# FE_Channel.net
KiCad netlist of a schematic drawn in Altium Designer
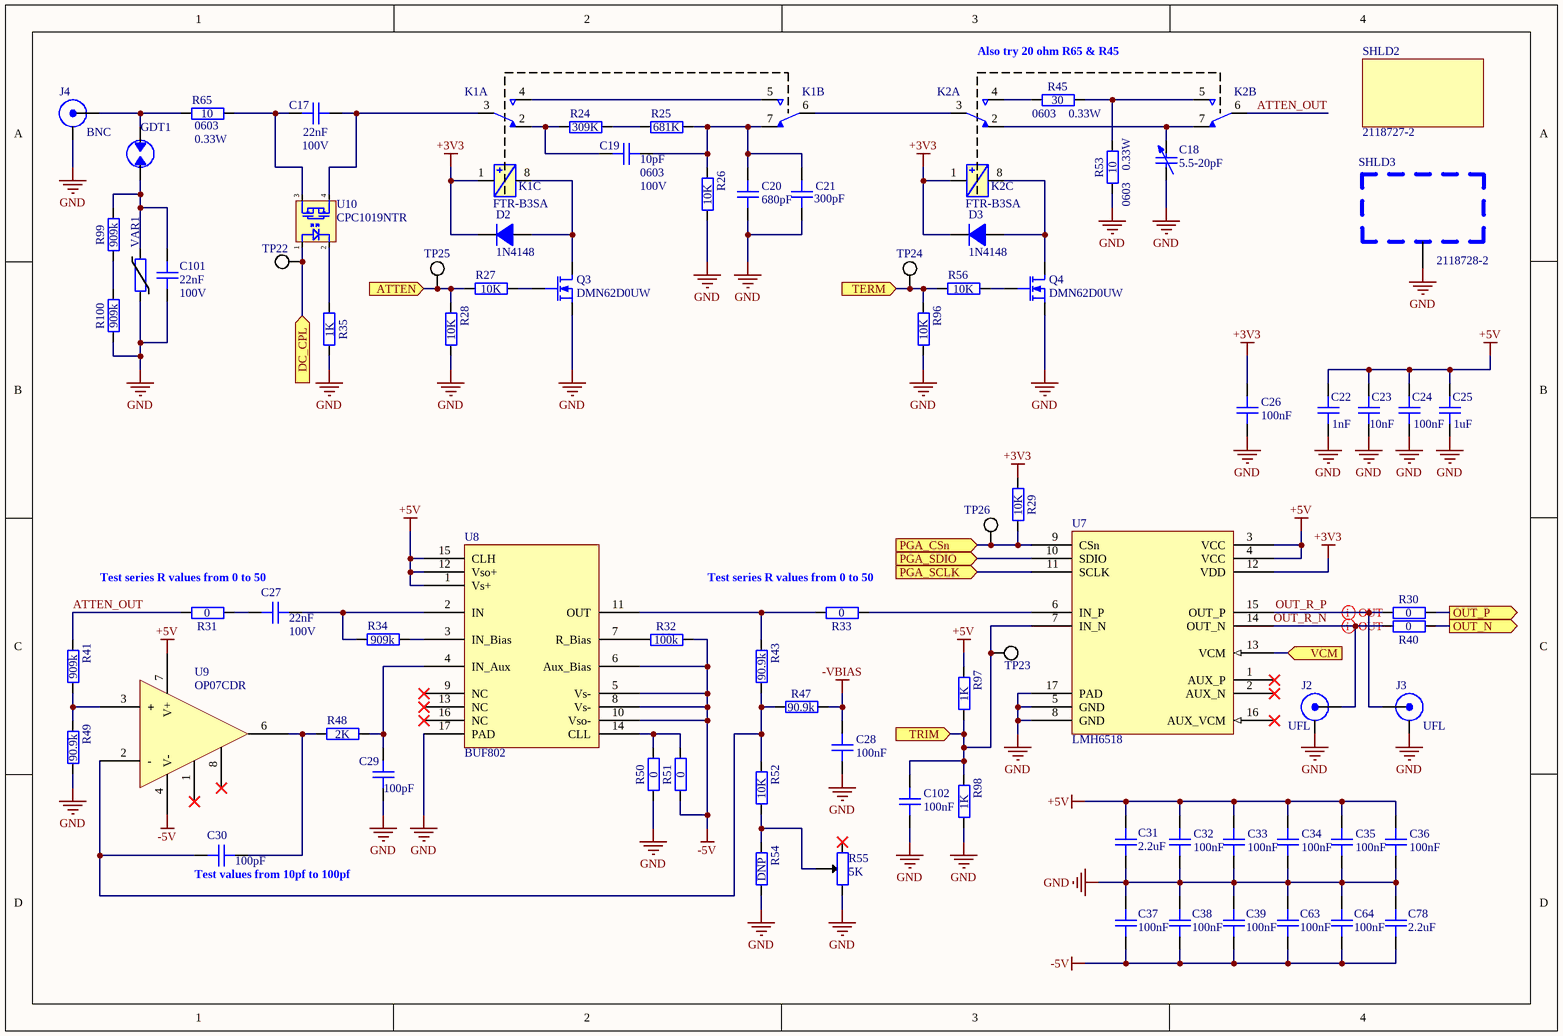
[diagram p0: FE_Channel.SchDoc]

(export (version "E")
  (design (tool "Eeschema 10.0.6"))
  (components
    (comp (ref "C17")
      (value "22nF")
      (footprint "GEN_C_0603")
      (fields (field (name "VOLTAGE RATING") "100V"))
      (libsource (lib "DSO") (part "CAP 22nF 100V X7R 0603"))
    )
    (comp (ref "C18")
      (value "5.5-20pF")
      (footprint "EW_TRIMCAP")
      (libsource (lib "DSO") (part "CAP TRIMMER 5.5-20PF 500V"))
    )
    (comp (ref "C19")
      (value "10pF")
      (footprint "GEN_C_0603")
      (fields (field (name "PACKAGE") "0603") (field (name "VOLTAGE RATING") "100V"))
      (libsource (lib "DSO") (part "CAP 10pF 100V C0G 0603"))
    )
    (comp (ref "C20")
      (value "680pF")
      (footprint "GEN_C_0402")
      (libsource (lib "DSO") (part "CAP 680pF 50V C0G 0402"))
    )
    (comp (ref "C21")
      (value "300pF")
      (footprint "GEN_C_0402")
      (libsource (lib "DSO") (part "CAP 300pF 50V C0G 0402"))
    )
    (comp (ref "C22")
      (value "1nF")
      (footprint "GEN_C_0402")
      (libsource (lib "DSO") (part "CAP 1nF 50V C0G 0402"))
    )
    (comp (ref "C23")
      (value "10nF")
      (footprint "GEN_C_0402")
      (libsource (lib "DSO") (part "CAP 10nF 50V X7R 0402"))
    )
    (comp (ref "C24")
      (value "100nF")
      (footprint "GEN_C_0402")
      (libsource (lib "DSO") (part "CAP 100nF 16V X7R 0402"))
    )
    (comp (ref "C25")
      (value "1uF")
      (footprint "GEN_C_0402")
      (libsource (lib "DSO") (part "CAP 1uF 25V X5R 0402"))
    )
    (comp (ref "C26")
      (value "100nF")
      (footprint "GEN_C_0402")
      (libsource (lib "DSO") (part "CAP 100nF 16V X7R 0402"))
    )
    (comp (ref "C27")
      (value "22nF")
      (footprint "GEN_C_0603")
      (fields (field (name "VOLTAGE RATING") "100V"))
      (libsource (lib "DSO") (part "CAP 22nF 100V X7R 0603"))
    )
    (comp (ref "C28")
      (value "100nF")
      (footprint "GEN_C_0402")
      (libsource (lib "DSO") (part "CAP 100nF 16V X7R 0402"))
    )
    (comp (ref "C29")
      (value "100pF")
      (footprint "GEN_C_0402")
      (libsource (lib "DSO") (part "CAP 100pF 50V C0G 0402"))
    )
    (comp (ref "C30")
      (value "100pF")
      (footprint "GEN_C_0402")
      (libsource (lib "DSO") (part "CAP 100pF 50V C0G 0402"))
    )
    (comp (ref "C31")
      (value "2.2uF")
      (footprint "GEN_C_0402")
      (libsource (lib "DSO") (part "CAP 2.2uF 10V X5R 0402"))
    )
    (comp (ref "C32")
      (value "100nF")
      (footprint "GEN_C_0402")
      (libsource (lib "DSO") (part "CAP 100nF 16V X7R 0402"))
    )
    (comp (ref "C33")
      (value "100nF")
      (footprint "GEN_C_0402")
      (libsource (lib "DSO") (part "CAP 100nF 16V X7R 0402"))
    )
    (comp (ref "C34")
      (value "100nF")
      (footprint "GEN_C_0402")
      (libsource (lib "DSO") (part "CAP 100nF 16V X7R 0402"))
    )
    (comp (ref "C35")
      (value "100nF")
      (footprint "GEN_C_0402")
      (libsource (lib "DSO") (part "CAP 100nF 16V X7R 0402"))
    )
    (comp (ref "C36")
      (value "100nF")
      (footprint "GEN_C_0402")
      (libsource (lib "DSO") (part "CAP 100nF 16V X7R 0402"))
    )
    (comp (ref "C37")
      (value "100nF")
      (footprint "GEN_C_0402")
      (libsource (lib "DSO") (part "CAP 100nF 16V X7R 0402"))
    )
    (comp (ref "C38")
      (value "100nF")
      (footprint "GEN_C_0402")
      (libsource (lib "DSO") (part "CAP 100nF 16V X7R 0402"))
    )
    (comp (ref "C39")
      (value "100nF")
      (footprint "GEN_C_0402")
      (libsource (lib "DSO") (part "CAP 100nF 16V X7R 0402"))
    )
    (comp (ref "C63")
      (value "100nF")
      (footprint "GEN_C_0402")
      (libsource (lib "DSO") (part "CAP 100nF 16V X7R 0402"))
    )
    (comp (ref "C64")
      (value "100nF")
      (footprint "GEN_C_0402")
      (libsource (lib "DSO") (part "CAP 100nF 16V X7R 0402"))
    )
    (comp (ref "C78")
      (value "2.2uF")
      (footprint "GEN_C_0402")
      (libsource (lib "DSO") (part "CAP 2.2uF 10V X5R 0402"))
    )
    (comp (ref "C101")
      (value "22nF")
      (footprint "GEN_C_0603")
      (fields (field (name "VOLTAGE RATING") "100V"))
      (libsource (lib "DSO") (part "CAP 22nF 100V X7R 0603"))
    )
    (comp (ref "C102")
      (value "100nF")
      (footprint "GEN_C_0402")
      (libsource (lib "DSO") (part "CAP 100nF 16V X7R 0402"))
    )
    (comp (ref "D2") (value "1N4148") (footprint "GEN_SOD_323") (libsource (lib "DSO") (part "DIODE 1N4148")))
    (comp (ref "D3") (value "1N4148") (footprint "GEN_SOD_323") (libsource (lib "DSO") (part "DIODE 1N4148")))
    (comp (ref "GDT1")
      (value "4532-075-LF")
      (footprint "BOU_2051")
      (libsource (lib "DSO") (part "GDT 75V 1812"))
    )
    (comp (ref "J2") (value "UFL") (footprint "TE_2334884-1") (libsource (lib "DSO") (part "UFL Jack SMD")))
    (comp (ref "J3") (value "UFL") (footprint "TE_2334884-1") (libsource (lib "DSO") (part "UFL Jack SMD")))
    (comp (ref "J4") (value "BNC") (footprint "MOL_0731000105") (libsource (lib "DSO") (part "BNC JACK R/A")))
    (comp (ref "K1")
      (value "FTR-B3SA")
      (footprint "FUJ_FTR-B3SA")
      (libsource (lib "DSO") (part "RELAY DPDT-NO FTR-B3SA"))
    )
    (comp (ref "K2")
      (value "FTR-B3SA")
      (footprint "FUJ_FTR-B3SA")
      (libsource (lib "") (part "RELAY DPDT-NO FTR-B3SA_1"))
    )
    (comp (ref "Q3")
      (value "DMN62D0UW")
      (footprint "GEN_SOT_323")
      (libsource (lib "DSO") (part "NMOS DMN62D0UW"))
    )
    (comp (ref "Q4")
      (value "DMN62D0UW")
      (footprint "GEN_SOT_323")
      (libsource (lib "DSO") (part "NMOS DMN62D0UW"))
    )
    (comp (ref "R24")
      (value "309K")
      (footprint "GEN_R_0402")
      (fields (field (name "TOLERANCE") "1%"))
      (libsource (lib "DSO") (part "RES 309K OHM 1% 1/16W 0402"))
    )
    (comp (ref "R25")
      (value "681K")
      (footprint "GEN_R_0402")
      (fields (field (name "TOLERANCE") "1%"))
      (libsource (lib "DSO") (part "RES 681K OHM 1% 1/16W 0402"))
    )
    (comp (ref "R26")
      (value "10K")
      (footprint "GEN_R_0402")
      (fields (field (name "TOLERANCE") "1%"))
      (libsource (lib "DSO") (part "RES 10K OHM 1% 1/10W 0402"))
    )
    (comp (ref "R27")
      (value "10K")
      (footprint "GEN_R_0402")
      (fields (field (name "TOLERANCE") "1%"))
      (libsource (lib "") (part "RES 10K OHM 1% 1/10W 0402_1"))
    )
    (comp (ref "R28")
      (value "10K")
      (footprint "GEN_R_0402")
      (fields (field (name "TOLERANCE") "1%"))
      (libsource (lib "DSO") (part "RES 10K OHM 1% 1/10W 0402"))
    )
    (comp (ref "R29")
      (value "10K")
      (footprint "GEN_R_0402")
      (fields (field (name "TOLERANCE") "1%"))
      (libsource (lib "DSO") (part "RES 10K OHM 1% 1/10W 0402"))
    )
    (comp (ref "R30")
      (value "0")
      (footprint "GEN_R_0402")
      (libsource (lib "") (part "RES 0 OHM 1/16W 0402_1"))
    )
    (comp (ref "R31")
      (value "0")
      (footprint "GEN_R_0402")
      (libsource (lib "") (part "RES 0 OHM 1/16W 0402_1"))
    )
    (comp (ref "R32")
      (value "100k")
      (footprint "GEN_R_0402")
      (fields (field (name "TOLERANCE") "1%"))
      (libsource (lib "DSO") (part "RES 100K OHM 1% 1/10W 0402"))
    )
    (comp (ref "R33")
      (value "0")
      (footprint "GEN_R_0402")
      (libsource (lib "") (part "RES 0 OHM 1/16W 0402_1"))
    )
    (comp (ref "R34")
      (value "909k")
      (footprint "GEN_R_0402")
      (fields (field (name "TOLERANCE") "1%"))
      (libsource (lib "") (part "RES 909K OHM 1% 1/16W 0402_1"))
    )
    (comp (ref "R35")
      (value "1K")
      (footprint "GEN_R_0402")
      (fields (field (name "TOLERANCE") "1%"))
      (libsource (lib "") (part "RES 1K OHM 1% 1/10W 0402_1"))
    )
    (comp (ref "R40")
      (value "0")
      (footprint "GEN_R_0402")
      (libsource (lib "") (part "RES 0 OHM 1/16W 0402_1"))
    )
    (comp (ref "R41")
      (value "909k")
      (footprint "GEN_R_0402")
      (fields (field (name "TOLERANCE") "1%"))
      (libsource (lib "DSO") (part "RES 909K OHM 1% 1/16W 0402"))
    )
    (comp (ref "R43")
      (value "90.9k")
      (footprint "GEN_R_0402")
      (fields (field (name "TOLERANCE") "1%"))
      (libsource (lib "") (part "RES 90.9K OHM 1% 1/16W 0402_1"))
    )
    (comp (ref "R45")
      (value "30")
      (footprint "GEN_R_0603")
      (fields
        (field (name "TOLERANCE") "1%")
        (field (name "POWER RATING") "0.33W")
        (field (name "PACKAGE") "0603")
      )
      (libsource (lib "DSO") (part "RES 30 OHM 1% 1/3W 0603"))
    )
    (comp (ref "R47")
      (value "90.9k")
      (footprint "GEN_R_0402")
      (fields (field (name "TOLERANCE") "1%"))
      (libsource (lib "DSO") (part "RES 90.9K OHM 1% 1/16W 0402"))
    )
    (comp (ref "R48")
      (value "2K")
      (footprint "GEN_R_0402")
      (fields (field (name "TOLERANCE") "1%"))
      (libsource (lib "DSO") (part "RES 2K OHM 1% 1/16W 0402"))
    )
    (comp (ref "R49")
      (value "90.9k")
      (footprint "GEN_R_0402")
      (fields (field (name "TOLERANCE") "1%"))
      (libsource (lib "") (part "RES 90.9K OHM 1% 1/16W 0402_1"))
    )
    (comp (ref "R50")
      (value "0")
      (footprint "GEN_R_0402")
      (libsource (lib "DSO") (part "RES 0 OHM 1/16W 0402"))
    )
    (comp (ref "R51")
      (value "0")
      (footprint "GEN_R_0402")
      (libsource (lib "DSO") (part "RES 0 OHM 1/16W 0402"))
    )
    (comp (ref "R52")
      (value "10K")
      (footprint "GEN_R_0402")
      (fields (field (name "TOLERANCE") "1%"))
      (libsource (lib "DSO") (part "RES 10K OHM 1% 1/10W 0402"))
    )
    (comp (ref "R53")
      (value "10")
      (footprint "GEN_R_0603")
      (fields
        (field (name "TOLERANCE") "1%")
        (field (name "POWER RATING") "0.33W")
        (field (name "PACKAGE") "0603")
      )
      (libsource (lib "") (part "RES 10 OHM 1% 1/3W 0603_1"))
    )
    (comp (ref "R54")
      (value "DNP")
      (footprint "GEN_R_0402")
      (fields (field (name "TOLERANCE") "1%"))
      (libsource (lib "DSO") (part "RES DNP 0402"))
    )
    (comp (ref "R55")
      (value "5K")
      (footprint "BOU_3mm_POT")
      (fields (field (name "TOLERANCE") "1%"))
      (libsource (lib "DSO") (part "TRIMMER 5K OHM 0.1W J LEAD TOP"))
    )
    (comp (ref "R56")
      (value "10K")
      (footprint "GEN_R_0402")
      (fields (field (name "TOLERANCE") "1%"))
      (libsource (lib "") (part "RES 10K OHM 1% 1/10W 0402_1"))
    )
    (comp (ref "R65")
      (value "10")
      (footprint "GEN_R_0603")
      (fields
        (field (name "PACKAGE") "0603")
        (field (name "TOLERANCE") "1%")
        (field (name "POWER RATING") "0.33W")
      )
      (libsource (lib "DSO") (part "RES 10 OHM 1% 1/3W 0603"))
    )
    (comp (ref "R96")
      (value "10K")
      (footprint "GEN_R_0402")
      (fields (field (name "TOLERANCE") "1%"))
      (libsource (lib "DSO") (part "RES 10K OHM 1% 1/10W 0402"))
    )
    (comp (ref "R97")
      (value "1K")
      (footprint "GEN_R_0402")
      (fields (field (name "TOLERANCE") "1%"))
      (libsource (lib "DSO") (part "RES 1K OHM 1% 1/10W 0402"))
    )
    (comp (ref "R98")
      (value "1K")
      (footprint "GEN_R_0402")
      (fields (field (name "TOLERANCE") "1%"))
      (libsource (lib "DSO") (part "RES 1K OHM 1% 1/10W 0402"))
    )
    (comp (ref "R99")
      (value "909k")
      (footprint "GEN_R_0402")
      (fields (field (name "TOLERANCE") "1%"))
      (libsource (lib "DSO") (part "RES 909K OHM 1% 1/16W 0402"))
    )
    (comp (ref "R100")
      (value "909k")
      (footprint "GEN_R_0402")
      (fields (field (name "TOLERANCE") "1%"))
      (libsource (lib "DSO") (part "RES 909K OHM 1% 1/16W 0402"))
    )
    (comp (ref "SHLD2") (value "2118727-2") (libsource (lib "DSO") (part "SHIELD 2118727-2")))
    (comp (ref "SHLD3")
      (value "2118728-2")
      (footprint "TE_2118728-2")
      (libsource (lib "DSO") (part "SHIELD 2118728-2"))
    )
    (comp (ref "TP22") (value "PCB") (footprint "GEN_TP_PCB") (libsource (lib "DSO") (part "TP PCB 1mm")))
    (comp (ref "TP23") (value "PCB") (footprint "GEN_TP_PCB") (libsource (lib "DSO") (part "TP PCB 1mm")))
    (comp (ref "TP24") (value "PCB") (footprint "GEN_TP_PCB") (libsource (lib "DSO") (part "TP PCB 1mm")))
    (comp (ref "TP25") (value "PCB") (footprint "GEN_TP_PCB") (libsource (lib "DSO") (part "TP PCB 1mm")))
    (comp (ref "TP26") (value "PCB") (footprint "GEN_TP_PCB") (libsource (lib "DSO") (part "TP PCB 1mm")))
    (comp (ref "U7")
      (value "LMH6518")
      (footprint "TI_WQFN_RGH0016A")
      (libsource (lib "DSO") (part "IC PGA LMH6518"))
    )
    (comp (ref "U8")
      (value "BUF802")
      (footprint "TI_VQFN_RGT0016C")
      (libsource (lib "DSO") (part "IC BUFFER AMP BUF802"))
    )
    (comp (ref "U9")
      (value "OP07CDR")
      (footprint "TI_SOIC8_D0008A")
      (libsource (lib "DSO") (part "IC OPAMP OP07CDR"))
    )
    (comp (ref "U10")
      (value "CPC1019NTR")
      (footprint "IXY_CPC1017")
      (libsource (lib "DSO") (part "SSR CPC1019NTR"))
    )
    (comp (ref "VAR1")
      (value "ZV40K1210251NIR1HT")
      (footprint "GEN_VAR_1210")
      (libsource (lib "DSO") (part "VARISTOR 68V 250A 1210"))
    )
  )
  (nets
    (net (code "1") (name "+3V3") (class "Default")
      (node (ref "C26") (pin "2") (pinfunction "2_2") (pintype "passive"))
      (node (ref "D2") (pin "1") (pinfunction "K_1") (pintype "passive"))
      (node (ref "D3") (pin "1") (pinfunction "K_1") (pintype "passive"))
      (node (ref "K1") (pin "1") (pinfunction "1_1") (pintype "passive"))
      (node (ref "K2") (pin "1") (pinfunction "1_1") (pintype "passive"))
      (node (ref "R29") (pin "2") (pinfunction "2_2") (pintype "passive"))
      (node (ref "U7") (pin "12") (pinfunction "VDD_12") (pintype "power_in"))
    )
    (net (code "2") (name "+5V") (class "Default")
      (node (ref "C22") (pin "2") (pinfunction "2_2") (pintype "passive"))
      (node (ref "C23") (pin "2") (pinfunction "2_2") (pintype "passive"))
      (node (ref "C24") (pin "2") (pinfunction "2_2") (pintype "passive"))
      (node (ref "C25") (pin "2") (pinfunction "2_2") (pintype "passive"))
      (node (ref "C31") (pin "2") (pinfunction "2_2") (pintype "passive"))
      (node (ref "C32") (pin "1") (pinfunction "1_1") (pintype "passive"))
      (node (ref "C33") (pin "1") (pinfunction "1_1") (pintype "passive"))
      (node (ref "C34") (pin "1") (pinfunction "1_1") (pintype "passive"))
      (node (ref "C35") (pin "2") (pinfunction "2_2") (pintype "passive"))
      (node (ref "C36") (pin "2") (pinfunction "2_2") (pintype "passive"))
      (node (ref "R97") (pin "2") (pinfunction "2_2") (pintype "passive"))
      (node (ref "U7") (pin "3") (pinfunction "VCC_3") (pintype "power_in"))
      (node (ref "U7") (pin "4") (pinfunction "VCC_4") (pintype "power_in"))
      (node (ref "U8") (pin "1") (pinfunction "Vs+_1") (pintype "passive"))
      (node (ref "U8") (pin "12") (pinfunction "Vso+_12") (pintype "passive"))
      (node (ref "U8") (pin "15") (pinfunction "CLH_15") (pintype "passive"))
      (node (ref "U9") (pin "7") (pinfunction "V+_7") (pintype "passive"))
    )
    (net (code "3") (name "-5V") (class "Default")
      (node (ref "C37") (pin "2") (pinfunction "2_2") (pintype "passive"))
      (node (ref "C38") (pin "2") (pinfunction "2_2") (pintype "passive"))
      (node (ref "C39") (pin "1") (pinfunction "1_1") (pintype "passive"))
      (node (ref "C63") (pin "1") (pinfunction "1_1") (pintype "passive"))
      (node (ref "C64") (pin "1") (pinfunction "1_1") (pintype "passive"))
      (node (ref "C78") (pin "2") (pinfunction "2_2") (pintype "passive"))
      (node (ref "R32") (pin "2") (pinfunction "2_2") (pintype "passive"))
      (node (ref "R51") (pin "1") (pinfunction "1_1") (pintype "passive"))
      (node (ref "U8") (pin "10") (pinfunction "Vso-_10") (pintype "passive"))
      (node (ref "U8") (pin "5") (pinfunction "Vs-_5") (pintype "passive"))
      (node (ref "U8") (pin "6") (pinfunction "Aux_Bias_6") (pintype "passive"))
      (node (ref "U8") (pin "8") (pinfunction "Vs-_8") (pintype "passive"))
      (node (ref "U9") (pin "4") (pinfunction "V-_4") (pintype "passive"))
    )
    (net (code "4") (name "-VBIAS") (class "Default")
      (node (ref "C28") (pin "1") (pinfunction "1_1") (pintype "passive"))
      (node (ref "R47") (pin "1") (pinfunction "1_1") (pintype "passive"))
    )
    (net (code "5") (name "/ATTEN") (class "Default")
      (node (ref "R27") (pin "2") (pinfunction "2_2") (pintype "passive"))
      (node (ref "R28") (pin "2") (pinfunction "2_2") (pintype "passive"))
      (node (ref "TP25") (pin "1") (pinfunction "1_1") (pintype "passive"))
    )
    (net (code "6") (name "/ATTEN_OUT") (class "Default")
      (node (ref "K2") (pin "6") (pinfunction "6_6") (pintype "passive"))
      (node (ref "R31") (pin "1") (pinfunction "1_1") (pintype "passive"))
      (node (ref "R41") (pin "2") (pinfunction "2_2") (pintype "passive"))
    )
    (net (code "7") (name "/DC_CPL") (class "Default")
      (node (ref "TP22") (pin "1") (pinfunction "1_1") (pintype "passive"))
      (node (ref "U10") (pin "1") (pinfunction "1_1") (pintype "passive"))
    )
    (net (code "8") (name "/OUT_N") (class "Default")
      (node (ref "R40") (pin "2") (pinfunction "2_2") (pintype "passive"))
    )
    (net (code "9") (name "/OUT_P") (class "Default")
      (node (ref "R30") (pin "2") (pinfunction "2_2") (pintype "passive"))
    )
    (net (code "10") (name "/OUT_R_N") (class "Default")
      (node (ref "J2") (pin "1") (pinfunction "Signal_1") (pintype "passive"))
      (node (ref "R40") (pin "1") (pinfunction "1_1") (pintype "passive"))
      (node (ref "U7") (pin "14") (pinfunction "OUT_N_14") (pintype "passive"))
    )
    (net (code "11") (name "/OUT_R_P") (class "Default")
      (node (ref "J3") (pin "1") (pinfunction "Signal_1") (pintype "passive"))
      (node (ref "R30") (pin "1") (pinfunction "1_1") (pintype "passive"))
      (node (ref "U7") (pin "15") (pinfunction "OUT_P_15") (pintype "passive"))
    )
    (net (code "12") (name "/PGA_CSn") (class "Default")
      (node (ref "R29") (pin "1") (pinfunction "1_1") (pintype "passive"))
      (node (ref "TP26") (pin "1") (pinfunction "1_1") (pintype "passive"))
      (node (ref "U7") (pin "9") (pinfunction "CSn_9") (pintype "passive"))
    )
    (net (code "13") (name "/PGA_SCLK") (class "Default")
      (node (ref "U7") (pin "11") (pinfunction "SCLK_11") (pintype "passive"))
    )
    (net (code "14") (name "/PGA_SDIO") (class "Default")
      (node (ref "U7") (pin "10") (pinfunction "SDIO_10") (pintype "passive"))
    )
    (net (code "15") (name "/TERM") (class "Default")
      (node (ref "R56") (pin "2") (pinfunction "2_2") (pintype "passive"))
      (node (ref "R96") (pin "2") (pinfunction "2_2") (pintype "passive"))
      (node (ref "TP24") (pin "1") (pinfunction "1_1") (pintype "passive"))
    )
    (net (code "16") (name "/TRIM") (class "Default")
      (node (ref "C102") (pin "1") (pinfunction "1_1") (pintype "passive"))
      (node (ref "R97") (pin "1") (pinfunction "1_1") (pintype "passive"))
      (node (ref "R98") (pin "2") (pinfunction "2_2") (pintype "passive"))
      (node (ref "TP23") (pin "1") (pinfunction "1_1") (pintype "passive"))
      (node (ref "U7") (pin "7") (pinfunction "IN_N_7") (pintype "passive"))
    )
    (net (code "17") (name "/VCM") (class "Default")
      (node (ref "U7") (pin "13") (pinfunction "VCM_13") (pintype "input"))
    )
    (net (code "18") (name "GND") (class "Default")
      (node (ref "C101") (pin "2") (pinfunction "2_2") (pintype "passive"))
      (node (ref "C102") (pin "2") (pinfunction "2_2") (pintype "passive"))
      (node (ref "C18") (pin "2") (pinfunction "2_2") (pintype "passive"))
      (node (ref "C20") (pin "1") (pinfunction "1_1") (pintype "passive"))
      (node (ref "C21") (pin "1") (pinfunction "1_1") (pintype "passive"))
      (node (ref "C22") (pin "1") (pinfunction "1_1") (pintype "passive"))
      (node (ref "C23") (pin "1") (pinfunction "1_1") (pintype "passive"))
      (node (ref "C24") (pin "1") (pinfunction "1_1") (pintype "passive"))
      (node (ref "C25") (pin "1") (pinfunction "1_1") (pintype "passive"))
      (node (ref "C26") (pin "1") (pinfunction "1_1") (pintype "passive"))
      (node (ref "C28") (pin "2") (pinfunction "2_2") (pintype "passive"))
      (node (ref "C29") (pin "1") (pinfunction "1_1") (pintype "passive"))
      (node (ref "C31") (pin "1") (pinfunction "1_1") (pintype "passive"))
      (node (ref "C32") (pin "2") (pinfunction "2_2") (pintype "passive"))
      (node (ref "C33") (pin "2") (pinfunction "2_2") (pintype "passive"))
      (node (ref "C34") (pin "2") (pinfunction "2_2") (pintype "passive"))
      (node (ref "C35") (pin "1") (pinfunction "1_1") (pintype "passive"))
      (node (ref "C36") (pin "1") (pinfunction "1_1") (pintype "passive"))
      (node (ref "C37") (pin "1") (pinfunction "1_1") (pintype "passive"))
      (node (ref "C38") (pin "1") (pinfunction "1_1") (pintype "passive"))
      (node (ref "C39") (pin "2") (pinfunction "2_2") (pintype "passive"))
      (node (ref "C63") (pin "2") (pinfunction "2_2") (pintype "passive"))
      (node (ref "C64") (pin "2") (pinfunction "2_2") (pintype "passive"))
      (node (ref "C78") (pin "1") (pinfunction "1_1") (pintype "passive"))
      (node (ref "J2") (pin "2") (pinfunction "SHIELD_2") (pintype "passive"))
      (node (ref "J3") (pin "2") (pinfunction "SHIELD_2") (pintype "passive"))
      (node (ref "J4") (pin "2") (pinfunction "SHIELD_2") (pintype "passive"))
      (node (ref "Q3") (pin "3") (pinfunction "S_3") (pintype "passive"))
      (node (ref "Q4") (pin "3") (pinfunction "S_3") (pintype "passive"))
      (node (ref "R100") (pin "1") (pinfunction "1_1") (pintype "passive"))
      (node (ref "R26") (pin "1") (pinfunction "1_1") (pintype "passive"))
      (node (ref "R28") (pin "1") (pinfunction "1_1") (pintype "passive"))
      (node (ref "R35") (pin "1") (pinfunction "1_1") (pintype "passive"))
      (node (ref "R49") (pin "1") (pinfunction "1_1") (pintype "passive"))
      (node (ref "R50") (pin "1") (pinfunction "1_1") (pintype "passive"))
      (node (ref "R53") (pin "1") (pinfunction "1_1") (pintype "passive"))
      (node (ref "R54") (pin "1") (pinfunction "1_1") (pintype "passive"))
      (node (ref "R55") (pin "3") (pinfunction "3_3") (pintype "passive"))
      (node (ref "R96") (pin "1") (pinfunction "1_1") (pintype "passive"))
      (node (ref "R98") (pin "1") (pinfunction "1_1") (pintype "passive"))
      (node (ref "SHLD3") (pin "1") (pinfunction "1_1") (pintype "passive"))
      (node (ref "U7") (pin "17") (pinfunction "PAD_17") (pintype "power_in"))
      (node (ref "U7") (pin "5") (pinfunction "GND_5") (pintype "power_in"))
      (node (ref "U7") (pin "8") (pinfunction "GND_8") (pintype "power_in"))
      (node (ref "U8") (pin "17") (pinfunction "PAD_17") (pintype "passive"))
      (node (ref "VAR1") (pin "1") (pinfunction "1_1") (pintype "passive"))
    )
    (net (code "19") (name "Net-(C17-Pad1)") (class "Default")
      (node (ref "C17") (pin "1") (pinfunction "1_1") (pintype "passive"))
      (node (ref "K1") (pin "3") (pinfunction "3_3") (pintype "passive"))
      (node (ref "U10") (pin "4") (pinfunction "4_4") (pintype "passive"))
    )
    (net (code "20") (name "Net-(C17-Pad2)") (class "Default")
      (node (ref "C17") (pin "2") (pinfunction "2_2") (pintype "passive"))
      (node (ref "R65") (pin "2") (pinfunction "2_2") (pintype "passive"))
      (node (ref "U10") (pin "3") (pinfunction "3_3") (pintype "passive"))
    )
    (net (code "21") (name "Net-(C18-Pad1)") (class "Default")
      (node (ref "C18") (pin "1") (pinfunction "1_1") (pintype "passive"))
      (node (ref "K2") (pin "2") (pinfunction "2_2") (pintype "passive"))
      (node (ref "K2") (pin "7") (pinfunction "7_7") (pintype "passive"))
    )
    (net (code "22") (name "Net-(C19-Pad1)") (class "Default")
      (node (ref "C19") (pin "1") (pinfunction "1_1") (pintype "passive"))
      (node (ref "C20") (pin "2") (pinfunction "2_2") (pintype "passive"))
      (node (ref "C21") (pin "2") (pinfunction "2_2") (pintype "passive"))
      (node (ref "K1") (pin "7") (pinfunction "7_7") (pintype "passive"))
      (node (ref "R25") (pin "2") (pinfunction "2_2") (pintype "passive"))
      (node (ref "R26") (pin "2") (pinfunction "2_2") (pintype "passive"))
    )
    (net (code "23") (name "Net-(C19-Pad2)") (class "Default")
      (node (ref "C19") (pin "2") (pinfunction "2_2") (pintype "passive"))
      (node (ref "K1") (pin "2") (pinfunction "2_2") (pintype "passive"))
      (node (ref "R24") (pin "1") (pinfunction "1_1") (pintype "passive"))
    )
    (net (code "24") (name "Net-(C27-Pad2)") (class "Default")
      (node (ref "C27") (pin "2") (pinfunction "2_2") (pintype "passive"))
      (node (ref "R31") (pin "2") (pinfunction "2_2") (pintype "passive"))
    )
    (net (code "25") (name "Net-(C101-Pad1)") (class "Default")
      (node (ref "C101") (pin "1") (pinfunction "1_1") (pintype "passive"))
      (node (ref "GDT1") (pin "2") (pinfunction "2_2") (pintype "passive"))
      (node (ref "R99") (pin "2") (pinfunction "2_2") (pintype "passive"))
      (node (ref "VAR1") (pin "2") (pinfunction "2_2") (pintype "passive"))
    )
    (net (code "26") (name "Net-(D2-A)") (class "Default")
      (node (ref "D2") (pin "2") (pinfunction "A_2") (pintype "passive"))
      (node (ref "K1") (pin "8") (pinfunction "8_8") (pintype "passive"))
      (node (ref "Q3") (pin "1") (pinfunction "D_1") (pintype "passive"))
    )
    (net (code "27") (name "Net-(D3-A)") (class "Default")
      (node (ref "D3") (pin "2") (pinfunction "A_2") (pintype "passive"))
      (node (ref "K2") (pin "8") (pinfunction "8_8") (pintype "passive"))
      (node (ref "Q4") (pin "1") (pinfunction "D_1") (pintype "passive"))
    )
    (net (code "28") (name "Net-(J4-Signal)") (class "Default")
      (node (ref "GDT1") (pin "1") (pinfunction "1_1") (pintype "passive"))
      (node (ref "J4") (pin "1") (pinfunction "Signal_1") (pintype "passive"))
      (node (ref "R65") (pin "1") (pinfunction "1_1") (pintype "passive"))
    )
    (net (code "29") (name "Net-(K1-Pad4)") (class "Default")
      (node (ref "K1") (pin "4") (pinfunction "4_4") (pintype "passive"))
      (node (ref "K1") (pin "5") (pinfunction "5_5") (pintype "passive"))
    )
    (net (code "30") (name "Net-(K1-Pad6)") (class "Default")
      (node (ref "K1") (pin "6") (pinfunction "6_6") (pintype "passive"))
      (node (ref "K2") (pin "3") (pinfunction "3_3") (pintype "passive"))
    )
    (net (code "31") (name "Net-(K2-Pad4)") (class "Default")
      (node (ref "K2") (pin "4") (pinfunction "4_4") (pintype "passive"))
      (node (ref "R45") (pin "1") (pinfunction "1_1") (pintype "passive"))
    )
    (net (code "32") (name "Net-(K2-Pad5)") (class "Default")
      (node (ref "K2") (pin "5") (pinfunction "5_5") (pintype "passive"))
      (node (ref "R45") (pin "2") (pinfunction "2_2") (pintype "passive"))
      (node (ref "R53") (pin "2") (pinfunction "2_2") (pintype "passive"))
    )
    (net (code "33") (name "Net-(Q3-G)") (class "Default")
      (node (ref "Q3") (pin "2") (pinfunction "G_2") (pintype "passive"))
      (node (ref "R27") (pin "1") (pinfunction "1_1") (pintype "passive"))
    )
    (net (code "34") (name "Net-(Q4-G)") (class "Default")
      (node (ref "Q4") (pin "2") (pinfunction "G_2") (pintype "passive"))
      (node (ref "R56") (pin "1") (pinfunction "1_1") (pintype "passive"))
    )
    (net (code "35") (name "Net-(R24-Pad2)") (class "Default")
      (node (ref "R24") (pin "2") (pinfunction "2_2") (pintype "passive"))
      (node (ref "R25") (pin "1") (pinfunction "1_1") (pintype "passive"))
    )
    (net (code "36") (name "Net-(R35-Pad2)") (class "Default")
      (node (ref "R35") (pin "2") (pinfunction "2_2") (pintype "passive"))
      (node (ref "U10") (pin "2") (pinfunction "2_2") (pintype "passive"))
    )
    (net (code "37") (name "Net-(R52-Pad1)") (class "Default")
      (node (ref "R52") (pin "1") (pinfunction "1_1") (pintype "passive"))
      (node (ref "R54") (pin "2") (pinfunction "2_2") (pintype "passive"))
      (node (ref "R55") (pin "2") (pinfunction "2_2") (pintype "passive"))
    )
    (net (code "38") (name "Net-(R100-Pad2)") (class "Default")
      (node (ref "R100") (pin "2") (pinfunction "2_2") (pintype "passive"))
      (node (ref "R99") (pin "1") (pinfunction "1_1") (pintype "passive"))
    )
    (net (code "39") (name "Net-(U7-IN_P)") (class "Default")
      (node (ref "R33") (pin "2") (pinfunction "2_2") (pintype "passive"))
      (node (ref "U7") (pin "6") (pinfunction "IN_P_6") (pintype "passive"))
    )
    (net (code "40") (name "Net-(U8-CLL)") (class "Default")
      (node (ref "R50") (pin "2") (pinfunction "2_2") (pintype "passive"))
      (node (ref "R51") (pin "2") (pinfunction "2_2") (pintype "passive"))
      (node (ref "U8") (pin "14") (pinfunction "CLL_14") (pintype "passive"))
    )
    (net (code "41") (name "Net-(U8-IN)") (class "Default")
      (node (ref "C27") (pin "1") (pinfunction "1_1") (pintype "passive"))
      (node (ref "R34") (pin "2") (pinfunction "2_2") (pintype "passive"))
      (node (ref "U8") (pin "2") (pinfunction "IN_2") (pintype "passive"))
    )
    (net (code "42") (name "Net-(U8-IN_Aux)") (class "Default")
      (node (ref "C29") (pin "2") (pinfunction "2_2") (pintype "passive"))
      (node (ref "R48") (pin "1") (pinfunction "1_1") (pintype "passive"))
      (node (ref "U8") (pin "4") (pinfunction "IN_Aux_4") (pintype "passive"))
    )
    (net (code "43") (name "Net-(U8-IN_Bias)") (class "Default")
      (node (ref "R34") (pin "1") (pinfunction "1_1") (pintype "passive"))
      (node (ref "U8") (pin "3") (pinfunction "IN_Bias_3") (pintype "passive"))
    )
    (net (code "44") (name "Net-(U8-OUT)") (class "Default")
      (node (ref "R33") (pin "1") (pinfunction "1_1") (pintype "passive"))
      (node (ref "R43") (pin "2") (pinfunction "2_2") (pintype "passive"))
      (node (ref "U8") (pin "11") (pinfunction "OUT_11") (pintype "passive"))
    )
    (net (code "45") (name "Net-(U8-R_Bias)") (class "Default")
      (node (ref "R32") (pin "1") (pinfunction "1_1") (pintype "passive"))
      (node (ref "U8") (pin "7") (pinfunction "R_Bias_7") (pintype "passive"))
    )
    (net (code "46") (name "Net-(U9-+)") (class "Default")
      (node (ref "R41") (pin "1") (pinfunction "1_1") (pintype "passive"))
      (node (ref "R49") (pin "2") (pinfunction "2_2") (pintype "passive"))
      (node (ref "U9") (pin "3") (pinfunction "+_3") (pintype "passive"))
    )
    (net (code "47") (name "Net-(U9--)") (class "Default")
      (node (ref "C30") (pin "2") (pinfunction "2_2") (pintype "passive"))
      (node (ref "R43") (pin "1") (pinfunction "1_1") (pintype "passive"))
      (node (ref "R47") (pin "2") (pinfunction "2_2") (pintype "passive"))
      (node (ref "R52") (pin "2") (pinfunction "2_2") (pintype "passive"))
      (node (ref "U9") (pin "2") (pinfunction "-_2") (pintype "passive"))
    )
    (net (code "48") (name "Net-(U9-OUT)") (class "Default")
      (node (ref "C30") (pin "1") (pinfunction "1_1") (pintype "passive"))
      (node (ref "R48") (pin "2") (pinfunction "2_2") (pintype "passive"))
      (node (ref "U9") (pin "6") (pinfunction "OUT_6") (pintype "passive"))
    )
    (net (code "49") (name "unconnected-(R55-Pad1)") (class "Default")
      (node (ref "R55") (pin "1") (pinfunction "1_1") (pintype "passive+no_connect"))
    )
    (net (code "50") (name "unconnected-(U7-AUX_N-Pad2)") (class "Default")
      (node (ref "U7") (pin "2") (pinfunction "AUX_N_2") (pintype "passive+no_connect"))
    )
    (net (code "51") (name "unconnected-(U7-AUX_P-Pad1)") (class "Default")
      (node (ref "U7") (pin "1") (pinfunction "AUX_P_1") (pintype "passive+no_connect"))
    )
    (net (code "52") (name "unconnected-(U7-AUX_VCM-Pad16)") (class "Default")
      (node (ref "U7") (pin "16") (pinfunction "AUX_VCM_16") (pintype "input+no_connect"))
    )
    (net (code "53") (name "unconnected-(U8-NC-Pad9)") (class "Default")
      (node (ref "U8") (pin "9") (pinfunction "NC_9") (pintype "passive+no_connect"))
    )
    (net (code "54") (name "unconnected-(U8-NC-Pad13)") (class "Default")
      (node (ref "U8") (pin "13") (pinfunction "NC_13") (pintype "passive+no_connect"))
    )
    (net (code "55") (name "unconnected-(U8-NC-Pad16)") (class "Default")
      (node (ref "U8") (pin "16") (pinfunction "NC_16") (pintype "passive+no_connect"))
    )
    (net (code "56") (name "unconnected-(U9-N1-Pad1)") (class "Default")
      (node (ref "U9") (pin "1") (pinfunction "N1_1") (pintype "passive+no_connect"))
    )
    (net (code "57") (name "unconnected-(U9-N2-Pad8)") (class "Default")
      (node (ref "U9") (pin "8") (pinfunction "N2_8") (pintype "passive+no_connect"))
    )
  )
)
